# ECU.net
KiCad netlist of a schematic drawn in EAGLE
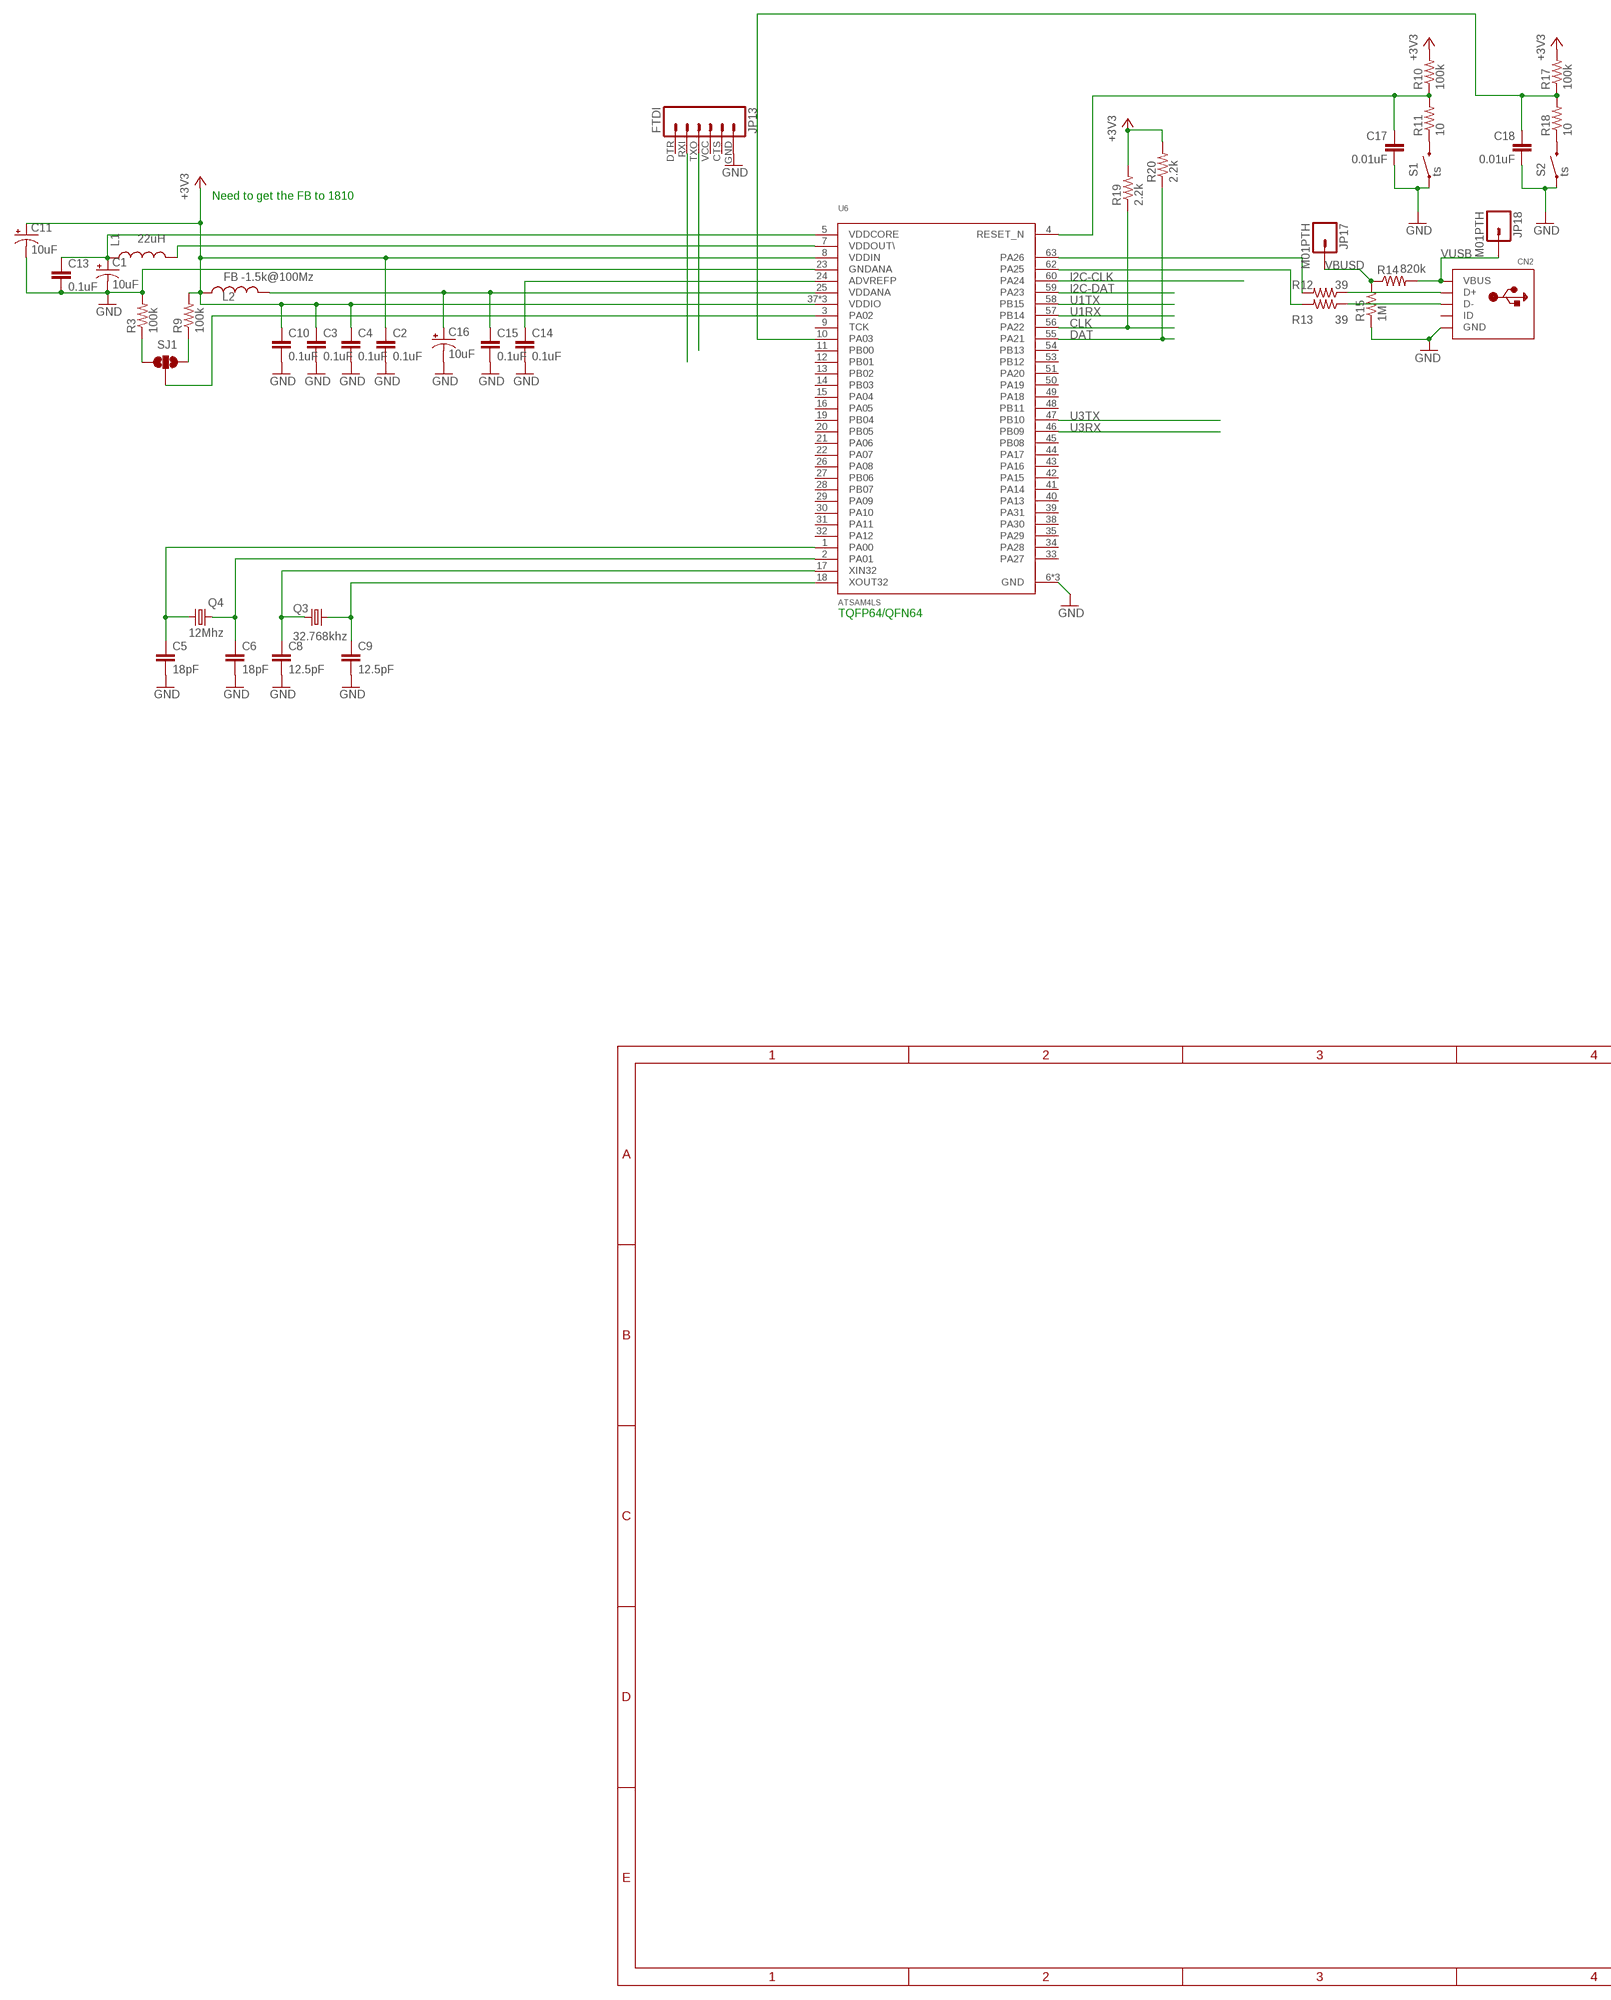
[diagram p0: schematic, sheet 1, part 1 of 2]
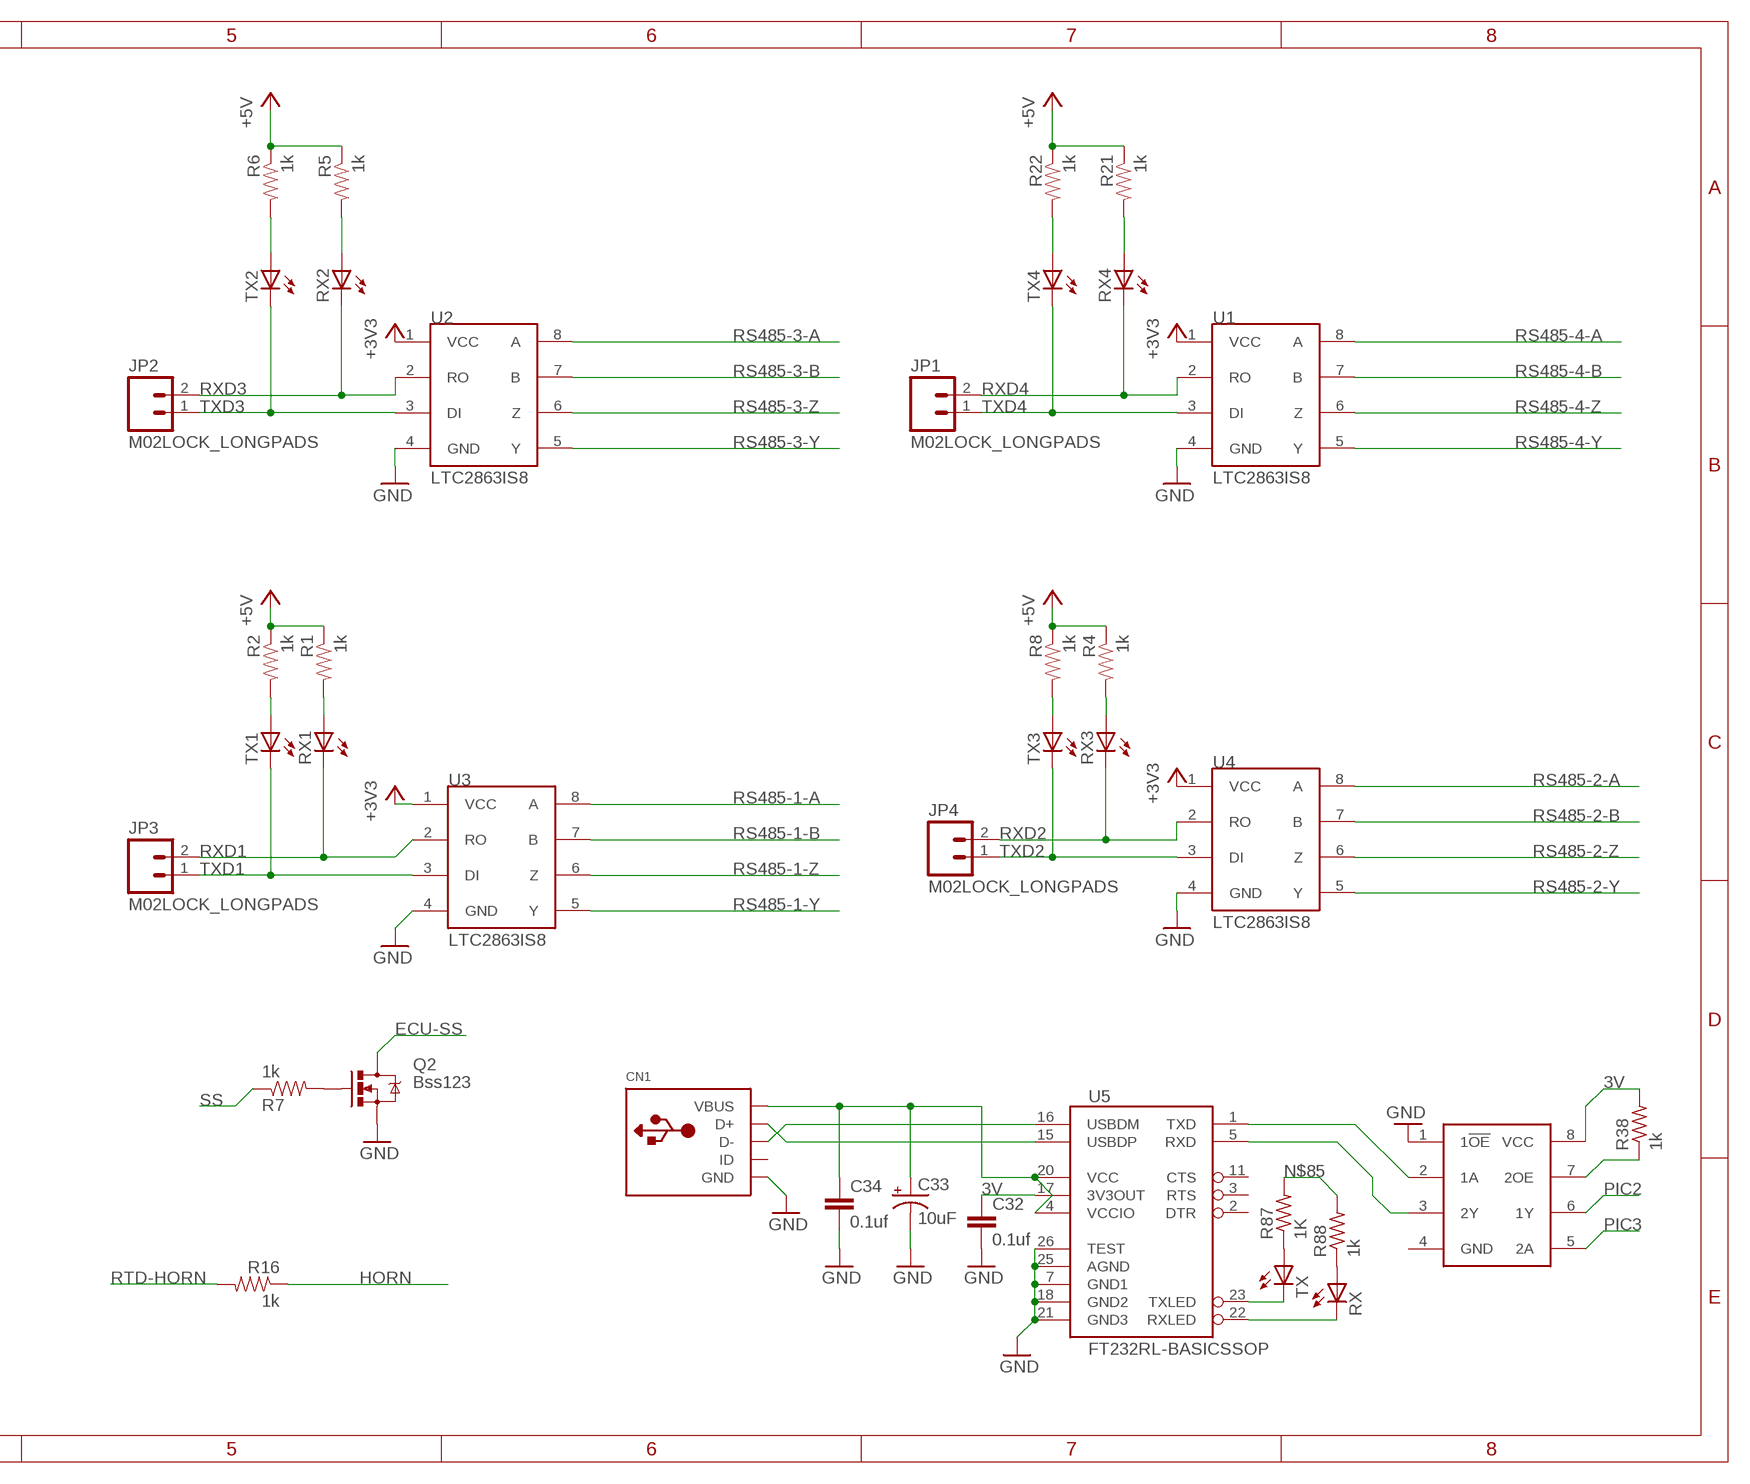
[diagram p1: schematic, sheet 1, part 2 of 2]
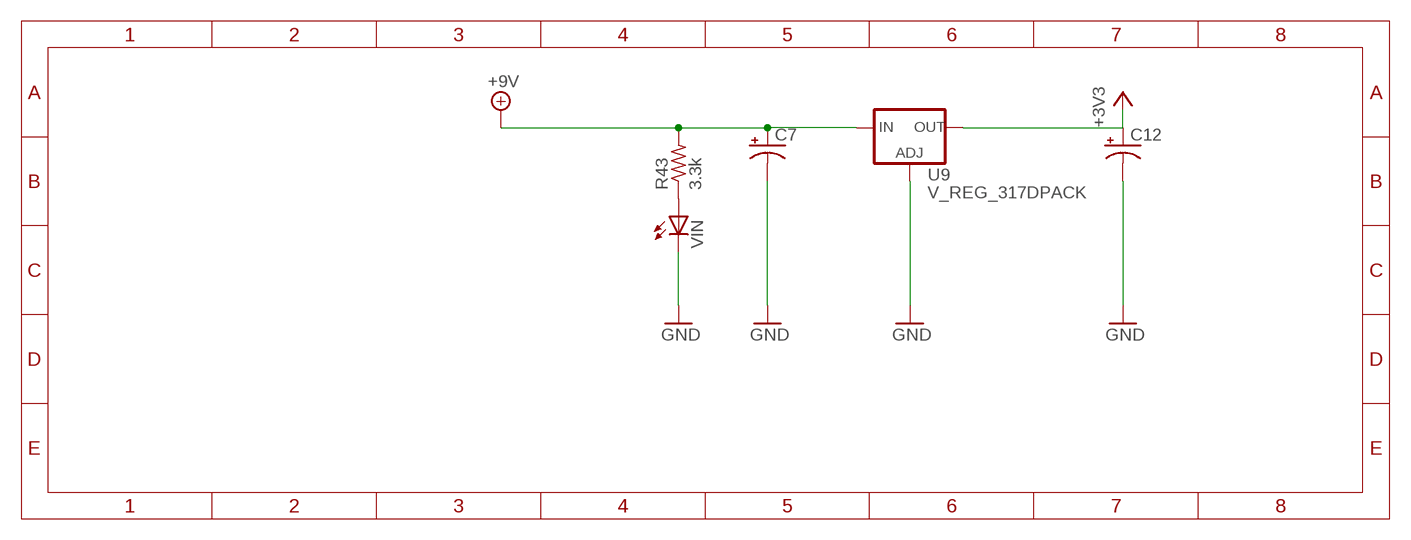
[diagram p2: schematic, sheet 2]
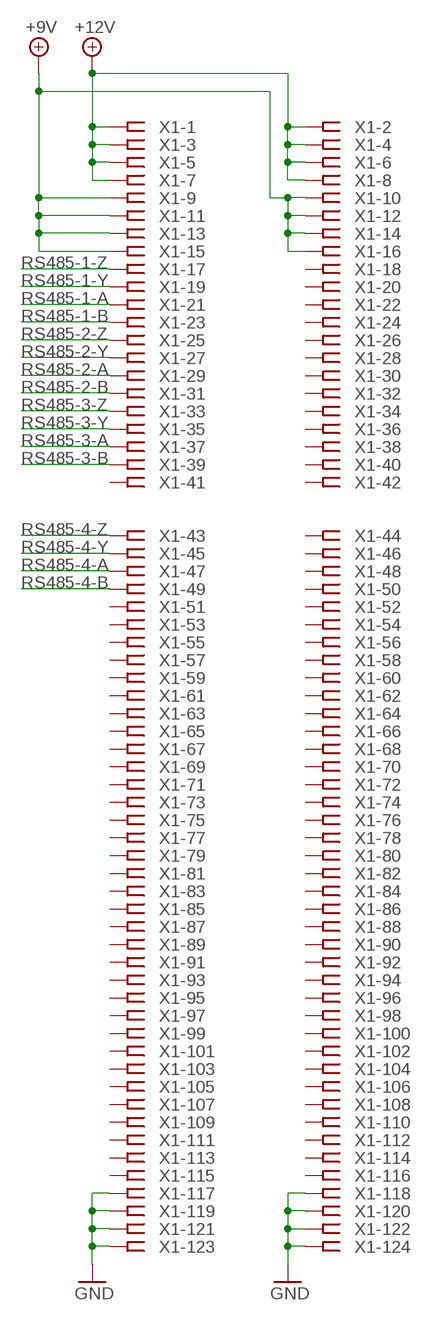
[diagram p3: schematic, sheet 3]

(export (version "E")
  (design (tool "Eeschema 10.0.6"))
  (components
    (comp (ref "X1")
      (value "AGP-3X3")
      (footprint "eagle-import:AGP-3X3")
      (libsource (lib "eagle-import") (part "AGP-3X3"))
    )
    (comp (ref "C7")
      (value "CAP_POL7343")
      (footprint "eagle-import:EIA7343")
      (libsource (lib "eagle-import") (part "SparkFun-Capacitors_CAP_POL7343"))
    )
    (comp (ref "C12")
      (value "CAP_POL3528")
      (footprint "eagle-import:EIA3528")
      (libsource (lib "eagle-import") (part "SparkFun-Capacitors_CAP_POL3528"))
    )
    (comp (ref "R43")
      (value "3.3k")
      (footprint "eagle-import:R0805")
      (libsource (lib "eagle-import") (part "R-US_R0805"))
    )
    (comp (ref "U9")
      (value "V_REG_317DPACK")
      (footprint "eagle-import:V-REG_DPACK")
      (libsource (lib "eagle-import") (part "V_REG_317DPACK"))
    )
    (comp (ref "VIN")
      (value "LEDCHIP-LED0805")
      (footprint "eagle-import:CHIP-LED0805")
      (libsource (lib "eagle-import") (part "LEDCHIP-LED0805"))
    )
    (comp (ref "C1")
      (value "10uF")
      (footprint "eagle-import:EIA3216")
      (libsource (lib "eagle-import") (part "SparkFun-Passives_CAP_POL1206"))
    )
    (comp (ref "C2")
      (value "0.1uF")
      (footprint "eagle-import:0805")
      (libsource (lib "eagle-import") (part "SparkFun-Passives_CAP0805"))
    )
    (comp (ref "C3")
      (value "0.1uF")
      (footprint "eagle-import:0805")
      (libsource (lib "eagle-import") (part "SparkFun-Passives_CAP0805"))
    )
    (comp (ref "C4")
      (value "0.1uF")
      (footprint "eagle-import:0805")
      (libsource (lib "eagle-import") (part "SparkFun-Passives_CAP0805"))
    )
    (comp (ref "C5")
      (value "18pF")
      (footprint "eagle-import:0805")
      (libsource (lib "eagle-import") (part "SparkFun-Passives_CAP0805"))
    )
    (comp (ref "C6")
      (value "18pF")
      (footprint "eagle-import:0805")
      (libsource (lib "eagle-import") (part "SparkFun-Passives_CAP0805"))
    )
    (comp (ref "C8")
      (value "12.5pF")
      (footprint "eagle-import:0805")
      (libsource (lib "eagle-import") (part "SparkFun-Passives_CAP0805"))
    )
    (comp (ref "C9")
      (value "12.5pF")
      (footprint "eagle-import:0805")
      (libsource (lib "eagle-import") (part "SparkFun-Passives_CAP0805"))
    )
    (comp (ref "C10")
      (value "0.1uF")
      (footprint "eagle-import:0805")
      (libsource (lib "eagle-import") (part "SparkFun-Passives_CAP0805"))
    )
    (comp (ref "C11")
      (value "10uF")
      (footprint "eagle-import:EIA3216")
      (libsource (lib "eagle-import") (part "10UF-16V-10%(TANT)"))
    )
    (comp (ref "C13")
      (value "0.1uF")
      (footprint "eagle-import:0805")
      (libsource (lib "eagle-import") (part "SparkFun-Passives_CAP0805"))
    )
    (comp (ref "C14")
      (value "0.1uF")
      (footprint "eagle-import:0805")
      (libsource (lib "eagle-import") (part "SparkFun-Passives_CAP0805"))
    )
    (comp (ref "C15")
      (value "0.1uF")
      (footprint "eagle-import:0805")
      (libsource (lib "eagle-import") (part "SparkFun-Passives_CAP0805"))
    )
    (comp (ref "C16")
      (value "10uF")
      (footprint "eagle-import:EIA3216")
      (libsource (lib "eagle-import") (part "SparkFun-Passives_CAP_POL1206"))
    )
    (comp (ref "C17")
      (value "0.01uF")
      (footprint "eagle-import:0805")
      (libsource (lib "eagle-import") (part "SparkFun-Passives_CAP0805"))
    )
    (comp (ref "C18")
      (value "0.01uF")
      (footprint "eagle-import:0805")
      (libsource (lib "eagle-import") (part "SparkFun-Passives_CAP0805"))
    )
    (comp (ref "C32")
      (value "0.1uf")
      (footprint "eagle-import:0805")
      (libsource (lib "eagle-import") (part "CAP0805"))
    )
    (comp (ref "C33")
      (value "10uF")
      (footprint "eagle-import:EIA3216")
      (libsource (lib "eagle-import") (part "CAP_POL1206"))
    )
    (comp (ref "C34")
      (value "0.1uf")
      (footprint "eagle-import:0805")
      (libsource (lib "eagle-import") (part "CAP0805"))
    )
    (comp (ref "CN1")
      (value "USBMOLEX")
      (footprint "eagle-import:USB-MINIB-THM-MOLEX")
      (libsource (lib "eagle-import") (part "USBMOLEX"))
    )
    (comp (ref "CN2")
      (value "USBMOLEX")
      (footprint "eagle-import:USB-MINIB-THM-MOLEX")
      (libsource (lib "eagle-import") (part "USBMOLEX"))
    )
    (comp (ref "JP1")
      (value "M02LOCK_LONGPADS")
      (footprint "eagle-import:1X02_LOCK_LONGPADS")
      (libsource (lib "eagle-import") (part "M02LOCK_LONGPADS"))
    )
    (comp (ref "JP2")
      (value "M02LOCK_LONGPADS")
      (footprint "eagle-import:1X02_LOCK_LONGPADS")
      (libsource (lib "eagle-import") (part "M02LOCK_LONGPADS"))
    )
    (comp (ref "JP3")
      (value "M02LOCK_LONGPADS")
      (footprint "eagle-import:1X02_LOCK_LONGPADS")
      (libsource (lib "eagle-import") (part "M02LOCK_LONGPADS"))
    )
    (comp (ref "JP4")
      (value "M02LOCK_LONGPADS")
      (footprint "eagle-import:1X02_LOCK_LONGPADS")
      (libsource (lib "eagle-import") (part "M02LOCK_LONGPADS"))
    )
    (comp (ref "JP13")
      (value "FTDI")
      (footprint "eagle-import:FTDI_BASIC")
      (libsource (lib "eagle-import") (part "FTDI_BASICPTH"))
    )
    (comp (ref "JP17")
      (value "M01PTH")
      (footprint "eagle-import:1X01")
      (libsource (lib "eagle-import") (part "M01PTH"))
    )
    (comp (ref "JP18")
      (value "M01PTH")
      (footprint "eagle-import:1X01")
      (libsource (lib "eagle-import") (part "M01PTH"))
    )
    (comp (ref "L1")
      (value "22uH")
      (footprint "eagle-import:0805")
      (libsource (lib "eagle-import") (part "INDUCTOR0805"))
    )
    (comp (ref "L2")
      (value "FB -1.5k@100Mz")
      (footprint "eagle-import:0805")
      (libsource (lib "eagle-import") (part "INDUCTOR0805"))
    )
    (comp (ref "Q2")
      (value "Bss123")
      (footprint "eagle-import:SOT23")
      (libsource (lib "eagle-import") (part "MOSFET-NCHANNELBSS123LT1G"))
    )
    (comp (ref "Q3")
      (value "32.768khz")
      (footprint "eagle-import:MM20SS")
      (libsource (lib "eagle-import") (part "CRYSTALMM20SS"))
    )
    (comp (ref "Q4")
      (value "12Mhz")
      (footprint "eagle-import:CTS406")
      (libsource (lib "eagle-import") (part "CRYSTALCTS406"))
    )
    (comp (ref "R1")
      (value "1k")
      (footprint "eagle-import:0805")
      (libsource (lib "eagle-import") (part "RESISTOR0805-RES"))
    )
    (comp (ref "R2")
      (value "1k")
      (footprint "eagle-import:0805")
      (libsource (lib "eagle-import") (part "RESISTOR0805-RES"))
    )
    (comp (ref "R3")
      (value "100k")
      (footprint "eagle-import:0805")
      (libsource (lib "eagle-import") (part "RESISTOR0805-RES"))
    )
    (comp (ref "R4")
      (value "1k")
      (footprint "eagle-import:0805")
      (libsource (lib "eagle-import") (part "RESISTOR0805-RES"))
    )
    (comp (ref "R5")
      (value "1k")
      (footprint "eagle-import:0805")
      (libsource (lib "eagle-import") (part "RESISTOR0805-RES"))
    )
    (comp (ref "R6")
      (value "1k")
      (footprint "eagle-import:0805")
      (libsource (lib "eagle-import") (part "RESISTOR0805-RES"))
    )
    (comp (ref "R7")
      (value "1k")
      (footprint "eagle-import:0805")
      (libsource (lib "eagle-import") (part "RESISTOR0805-RES"))
    )
    (comp (ref "R8")
      (value "1k")
      (footprint "eagle-import:0805")
      (libsource (lib "eagle-import") (part "RESISTOR0805-RES"))
    )
    (comp (ref "R9")
      (value "100k")
      (footprint "eagle-import:0805")
      (libsource (lib "eagle-import") (part "RESISTOR0805-RES"))
    )
    (comp (ref "R10")
      (value "100k")
      (footprint "eagle-import:0805")
      (libsource (lib "eagle-import") (part "RESISTOR0805-RES"))
    )
    (comp (ref "R11")
      (value "10")
      (footprint "eagle-import:0805")
      (libsource (lib "eagle-import") (part "RESISTOR0805-RES"))
    )
    (comp (ref "R12")
      (value "39")
      (footprint "eagle-import:0805")
      (libsource (lib "eagle-import") (part "RESISTOR0805-RES"))
    )
    (comp (ref "R13")
      (value "39")
      (footprint "eagle-import:0805")
      (libsource (lib "eagle-import") (part "RESISTOR0805-RES"))
    )
    (comp (ref "R14")
      (value "820k")
      (footprint "eagle-import:0805")
      (libsource (lib "eagle-import") (part "RESISTOR0805-RES"))
    )
    (comp (ref "R15")
      (value "1M")
      (footprint "eagle-import:0805")
      (libsource (lib "eagle-import") (part "RESISTOR0805-RES"))
    )
    (comp (ref "R16")
      (value "1k")
      (footprint "eagle-import:0805")
      (libsource (lib "eagle-import") (part "RESISTOR0805-RES"))
    )
    (comp (ref "R17")
      (value "100k")
      (footprint "eagle-import:0805")
      (libsource (lib "eagle-import") (part "RESISTOR0805-RES"))
    )
    (comp (ref "R18")
      (value "10")
      (footprint "eagle-import:0805")
      (libsource (lib "eagle-import") (part "RESISTOR0805-RES"))
    )
    (comp (ref "R19")
      (value "2.2k")
      (footprint "eagle-import:0805")
      (libsource (lib "eagle-import") (part "RESISTOR0805-RES"))
    )
    (comp (ref "R20")
      (value "2.2k")
      (footprint "eagle-import:0805")
      (libsource (lib "eagle-import") (part "RESISTOR0805-RES"))
    )
    (comp (ref "R21")
      (value "1k")
      (footprint "eagle-import:0805")
      (libsource (lib "eagle-import") (part "RESISTOR0805-RES"))
    )
    (comp (ref "R22")
      (value "1k")
      (footprint "eagle-import:0805")
      (libsource (lib "eagle-import") (part "RESISTOR0805-RES"))
    )
    (comp (ref "R38")
      (value "1k")
      (footprint "eagle-import:R0805")
      (libsource (lib "eagle-import") (part "R-US_R0805"))
    )
    (comp (ref "R87")
      (value "1K")
      (footprint "eagle-import:R0805")
      (libsource (lib "eagle-import") (part "R-US_R0805"))
    )
    (comp (ref "R88")
      (value "1k")
      (footprint "eagle-import:R0805")
      (libsource (lib "eagle-import") (part "R-US_R0805"))
    )
    (comp (ref "RX")
      (value "LEDCHIPLED_0805")
      (footprint "eagle-import:CHIPLED_0805")
      (libsource (lib "eagle-import") (part "LEDCHIPLED_0805"))
    )
    (comp (ref "RX1")
      (value "LEDCHIP-LED0805")
      (footprint "eagle-import:CHIP-LED0805")
      (libsource (lib "eagle-import") (part "LEDCHIP-LED0805"))
    )
    (comp (ref "RX2")
      (value "LEDCHIP-LED0805")
      (footprint "eagle-import:CHIP-LED0805")
      (libsource (lib "eagle-import") (part "LEDCHIP-LED0805"))
    )
    (comp (ref "RX3")
      (value "LEDCHIP-LED0805")
      (footprint "eagle-import:CHIP-LED0805")
      (libsource (lib "eagle-import") (part "LEDCHIP-LED0805"))
    )
    (comp (ref "RX4")
      (value "LEDCHIP-LED0805")
      (footprint "eagle-import:CHIP-LED0805")
      (libsource (lib "eagle-import") (part "LEDCHIP-LED0805"))
    )
    (comp (ref "S1")
      (value "ts")
      (footprint "eagle-import:TACTILE-PTH-SIDEEZ")
      (libsource (lib "eagle-import") (part "SWITCH-MOMENTARY-2SIDE_EZ"))
    )
    (comp (ref "S2")
      (value "ts")
      (footprint "eagle-import:TACTILE-PTH-SIDEEZ")
      (libsource (lib "eagle-import") (part "SWITCH-MOMENTARY-2SIDE_EZ"))
    )
    (comp (ref "SJ1")
      (value "SOLDERJUMPER_2WAYS")
      (footprint "eagle-import:SJ_3")
      (libsource (lib "eagle-import") (part "SOLDERJUMPER_2WAYS"))
    )
    (comp (ref "TX")
      (value "LEDCHIPLED_0805")
      (footprint "eagle-import:CHIPLED_0805")
      (libsource (lib "eagle-import") (part "LEDCHIPLED_0805"))
    )
    (comp (ref "TX1")
      (value "LEDCHIP-LED0805")
      (footprint "eagle-import:CHIP-LED0805")
      (libsource (lib "eagle-import") (part "LEDCHIP-LED0805"))
    )
    (comp (ref "TX2")
      (value "LEDCHIP-LED0805")
      (footprint "eagle-import:CHIP-LED0805")
      (libsource (lib "eagle-import") (part "LEDCHIP-LED0805"))
    )
    (comp (ref "TX3")
      (value "LEDCHIP-LED0805")
      (footprint "eagle-import:CHIP-LED0805")
      (libsource (lib "eagle-import") (part "LEDCHIP-LED0805"))
    )
    (comp (ref "TX4")
      (value "LEDCHIP-LED0805")
      (footprint "eagle-import:CHIP-LED0805")
      (libsource (lib "eagle-import") (part "LEDCHIP-LED0805"))
    )
    (comp (ref "U1")
      (value "LTC2863IS8")
      (footprint "eagle-import:SO08")
      (libsource (lib "eagle-import") (part "ISL83077"))
    )
    (comp (ref "U2")
      (value "LTC2863IS8")
      (footprint "eagle-import:SO08")
      (libsource (lib "eagle-import") (part "ISL83077"))
    )
    (comp (ref "U3")
      (value "LTC2863IS8")
      (footprint "eagle-import:SO08")
      (libsource (lib "eagle-import") (part "ISL83077"))
    )
    (comp (ref "U4")
      (value "LTC2863IS8")
      (footprint "eagle-import:SO08")
      (libsource (lib "eagle-import") (part "ISL83077"))
    )
    (comp (ref "U5")
      (value "FT232RL-BASICSSOP")
      (footprint "eagle-import:SSOP28DB")
      (libsource (lib "eagle-import") (part "FT232RL-BASICSSOP"))
    )
    (comp (ref "U6")
      (value "ATSAM4LS")
      (footprint "eagle-import:TQFP-64")
      (libsource (lib "eagle-import") (part "SAM4L"))
    )
    (comp (ref "U14")
      (value "SN74LVC2G241DCTR")
      (footprint "eagle-import:VFSOP-8")
      (libsource (lib "eagle-import") (part "SN74LVC2G241DCTR"))
    )
  )
  (nets
    (net (code "1") (name "+3V3") (class "Default")
      (node (ref "C10") (pin "1") (pinfunction "1_1") (pintype "passive"))
      (node (ref "C11") (pin "A") (pinfunction "+_A") (pintype "passive"))
      (node (ref "C12") (pin "A") (pinfunction "+_A") (pintype "passive"))
      (node (ref "C2") (pin "1") (pinfunction "1_1") (pintype "passive"))
      (node (ref "C3") (pin "1") (pinfunction "1_1") (pintype "passive"))
      (node (ref "C4") (pin "1") (pinfunction "1_1") (pintype "passive"))
      (node (ref "L2") (pin "1") (pinfunction "1_1") (pintype "passive"))
      (node (ref "R10") (pin "2") (pinfunction "2_2") (pintype "passive"))
      (node (ref "R17") (pin "2") (pinfunction "2_2") (pintype "passive"))
      (node (ref "R19") (pin "2") (pinfunction "2_2") (pintype "passive"))
      (node (ref "R20") (pin "2") (pinfunction "2_2") (pintype "passive"))
      (node (ref "R9") (pin "2") (pinfunction "2_2") (pintype "passive"))
      (node (ref "U1") (pin "1") (pinfunction "VCC_1") (pintype "bidirectional"))
      (node (ref "U2") (pin "1") (pinfunction "VCC_1") (pintype "bidirectional"))
      (node (ref "U3") (pin "1") (pinfunction "VCC_1") (pintype "bidirectional"))
      (node (ref "U4") (pin "1") (pinfunction "VCC_1") (pintype "bidirectional"))
      (node (ref "U6") (pin "37") (pinfunction "VDDIO_37") (pintype "bidirectional"))
      (node (ref "U6") (pin "52") (pinfunction "VDDIO_52") (pintype "bidirectional"))
      (node (ref "U6") (pin "61") (pinfunction "VDDIO_61") (pintype "bidirectional"))
      (node (ref "U6") (pin "8") (pinfunction "VDDIN_8") (pintype "bidirectional"))
      (node (ref "U9") (pin "4") (pinfunction "OUT_4") (pintype "output"))
    )
    (net (code "2") (name "+5V") (class "Default")
      (node (ref "R1") (pin "1") (pinfunction "1_1") (pintype "passive"))
      (node (ref "R2") (pin "1") (pinfunction "1_1") (pintype "passive"))
      (node (ref "R21") (pin "1") (pinfunction "1_1") (pintype "passive"))
      (node (ref "R22") (pin "1") (pinfunction "1_1") (pintype "passive"))
      (node (ref "R4") (pin "1") (pinfunction "1_1") (pintype "passive"))
      (node (ref "R5") (pin "1") (pinfunction "1_1") (pintype "passive"))
      (node (ref "R6") (pin "1") (pinfunction "1_1") (pintype "passive"))
      (node (ref "R8") (pin "1") (pinfunction "1_1") (pintype "passive"))
    )
    (net (code "3") (name "+9V") (class "Default")
      (node (ref "C7") (pin "A") (pinfunction "+_A") (pintype "passive"))
      (node (ref "R43") (pin "2") (pinfunction "2_2") (pintype "passive"))
      (node (ref "U9") (pin "3") (pinfunction "IN_3") (pintype "input"))
      (node (ref "X1") (pin "10") (pinfunction "P_10") (pintype "passive"))
      (node (ref "X1") (pin "11") (pinfunction "P_11") (pintype "passive"))
      (node (ref "X1") (pin "12") (pinfunction "P_12") (pintype "passive"))
      (node (ref "X1") (pin "13") (pinfunction "P_13") (pintype "passive"))
      (node (ref "X1") (pin "14") (pinfunction "P_14") (pintype "passive"))
      (node (ref "X1") (pin "15") (pinfunction "P_15") (pintype "passive"))
      (node (ref "X1") (pin "16") (pinfunction "P_16") (pintype "passive"))
      (node (ref "X1") (pin "9") (pinfunction "P_9") (pintype "passive"))
    )
    (net (code "4") (name "+12V") (class "Default")
      (node (ref "X1") (pin "1") (pinfunction "P_1") (pintype "passive"))
      (node (ref "X1") (pin "2") (pinfunction "P_2") (pintype "passive"))
      (node (ref "X1") (pin "3") (pinfunction "P_3") (pintype "passive"))
      (node (ref "X1") (pin "4") (pinfunction "P_4") (pintype "passive"))
      (node (ref "X1") (pin "5") (pinfunction "P_5") (pintype "passive"))
      (node (ref "X1") (pin "6") (pinfunction "P_6") (pintype "passive"))
      (node (ref "X1") (pin "7") (pinfunction "P_7") (pintype "passive"))
      (node (ref "X1") (pin "8") (pinfunction "P_8") (pintype "passive"))
    )
    (net (code "5") (name "3V") (class "Default")
      (node (ref "C32") (pin "1") (pinfunction "1_1") (pintype "passive"))
      (node (ref "R38") (pin "2") (pinfunction "2_2") (pintype "passive"))
      (node (ref "U14") (pin "8") (pinfunction "VCC_8") (pintype "bidirectional"))
      (node (ref "U5") (pin "17") (pinfunction "3V3OUT_17") (pintype "output"))
    )
    (net (code "6") (name "CLK") (class "Default")
      (node (ref "R19") (pin "1") (pinfunction "1_1") (pintype "passive"))
      (node (ref "U6") (pin "56") (pinfunction "PA22_56") (pintype "bidirectional"))
    )
    (net (code "7") (name "DAT") (class "Default")
      (node (ref "R20") (pin "1") (pinfunction "1_1") (pintype "passive"))
      (node (ref "U6") (pin "55") (pinfunction "PA21_55") (pintype "bidirectional"))
    )
    (net (code "8") (name "ECU-SS") (class "Default")
      (node (ref "Q2") (pin "3") (pinfunction "D_3") (pintype "passive"))
    )
    (net (code "9") (name "GND") (class "Default")
      (node (ref "C1") (pin "C") (pinfunction "-_C") (pintype "passive"))
      (node (ref "C10") (pin "2") (pinfunction "2_2") (pintype "passive"))
      (node (ref "C11") (pin "C") (pinfunction "-_C") (pintype "passive"))
      (node (ref "C12") (pin "C") (pinfunction "-_C") (pintype "passive"))
      (node (ref "C13") (pin "2") (pinfunction "2_2") (pintype "passive"))
      (node (ref "C14") (pin "2") (pinfunction "2_2") (pintype "passive"))
      (node (ref "C15") (pin "2") (pinfunction "2_2") (pintype "passive"))
      (node (ref "C16") (pin "C") (pinfunction "-_C") (pintype "passive"))
      (node (ref "C17") (pin "2") (pinfunction "2_2") (pintype "passive"))
      (node (ref "C18") (pin "2") (pinfunction "2_2") (pintype "passive"))
      (node (ref "C2") (pin "2") (pinfunction "2_2") (pintype "passive"))
      (node (ref "C3") (pin "2") (pinfunction "2_2") (pintype "passive"))
      (node (ref "C32") (pin "2") (pinfunction "2_2") (pintype "passive"))
      (node (ref "C33") (pin "C") (pinfunction "-_C") (pintype "passive"))
      (node (ref "C34") (pin "2") (pinfunction "2_2") (pintype "passive"))
      (node (ref "C4") (pin "2") (pinfunction "2_2") (pintype "passive"))
      (node (ref "C5") (pin "2") (pinfunction "2_2") (pintype "passive"))
      (node (ref "C6") (pin "2") (pinfunction "2_2") (pintype "passive"))
      (node (ref "C7") (pin "C") (pinfunction "-_C") (pintype "passive"))
      (node (ref "C8") (pin "2") (pinfunction "2_2") (pintype "passive"))
      (node (ref "C9") (pin "2") (pinfunction "2_2") (pintype "passive"))
      (node (ref "CN1") (pin "GND") (pinfunction "GND_GND") (pintype "power_in"))
      (node (ref "CN2") (pin "GND") (pinfunction "GND_GND") (pintype "power_in"))
      (node (ref "JP13") (pin "GND") (pinfunction "6_GND") (pintype "passive"))
      (node (ref "Q2") (pin "2") (pinfunction "S_2") (pintype "passive"))
      (node (ref "R15") (pin "1") (pinfunction "1_1") (pintype "passive"))
      (node (ref "R3") (pin "2") (pinfunction "2_2") (pintype "passive"))
      (node (ref "S1") (pin "1") (pinfunction "1_1") (pintype "passive"))
      (node (ref "S2") (pin "1") (pinfunction "1_1") (pintype "passive"))
      (node (ref "U1") (pin "4") (pinfunction "GND_4") (pintype "bidirectional"))
      (node (ref "U14") (pin "1") (pinfunction "1~{OE}_1") (pintype "bidirectional"))
      (node (ref "U2") (pin "4") (pinfunction "GND_4") (pintype "bidirectional"))
      (node (ref "U3") (pin "4") (pinfunction "GND_4") (pintype "bidirectional"))
      (node (ref "U4") (pin "4") (pinfunction "GND_4") (pintype "bidirectional"))
      (node (ref "U5") (pin "18") (pinfunction "GND2_18") (pintype "power_in"))
      (node (ref "U5") (pin "21") (pinfunction "GND3_21") (pintype "power_in"))
      (node (ref "U5") (pin "25") (pinfunction "AGND_25") (pintype "power_in"))
      (node (ref "U5") (pin "26") (pinfunction "TEST_26") (pintype "input"))
      (node (ref "U5") (pin "7") (pinfunction "GND1_7") (pintype "power_in"))
      (node (ref "U6") (pin "23") (pinfunction "GNDANA_23") (pintype "bidirectional"))
      (node (ref "U6") (pin "36") (pinfunction "GND_36") (pintype "bidirectional"))
      (node (ref "U6") (pin "6") (pinfunction "GND_6") (pintype "bidirectional"))
      (node (ref "U6") (pin "64") (pinfunction "GND_64") (pintype "bidirectional"))
      (node (ref "U9") (pin "1") (pinfunction "ADJ_1") (pintype "input"))
      (node (ref "VIN") (pin "C") (pinfunction "C_C") (pintype "passive"))
      (node (ref "X1") (pin "117") (pinfunction "P_117") (pintype "passive"))
      (node (ref "X1") (pin "118") (pinfunction "P_118") (pintype "passive"))
      (node (ref "X1") (pin "119") (pinfunction "P_119") (pintype "passive"))
      (node (ref "X1") (pin "120") (pinfunction "P_120") (pintype "passive"))
      (node (ref "X1") (pin "121") (pinfunction "P_121") (pintype "passive"))
      (node (ref "X1") (pin "122") (pinfunction "P_122") (pintype "passive"))
      (node (ref "X1") (pin "123") (pinfunction "P_123") (pintype "passive"))
      (node (ref "X1") (pin "124") (pinfunction "P_124") (pintype "passive"))
    )
    (net (code "10") (name "HORN") (class "Default")
      (node (ref "R16") (pin "1") (pinfunction "1_1") (pintype "passive"))
    )
    (net (code "11") (name "I2C-CLK") (class "Default")
      (node (ref "U6") (pin "60") (pinfunction "PA24_60") (pintype "bidirectional"))
    )
    (net (code "12") (name "I2C-DAT") (class "Default")
      (node (ref "U6") (pin "59") (pinfunction "PA23_59") (pintype "bidirectional"))
    )
    (net (code "13") (name "N$85") (class "Default")
      (node (ref "C33") (pin "A") (pinfunction "+_A") (pintype "passive"))
      (node (ref "C34") (pin "1") (pinfunction "1_1") (pintype "passive"))
      (node (ref "CN1") (pin "VBUS") (pinfunction "VBUS_VBUS") (pintype "power_in"))
      (node (ref "R87") (pin "2") (pinfunction "2_2") (pintype "passive"))
      (node (ref "R88") (pin "2") (pinfunction "2_2") (pintype "passive"))
      (node (ref "U5") (pin "20") (pinfunction "VCC_20") (pintype "power_in"))
      (node (ref "U5") (pin "4") (pinfunction "VCCIO_4") (pintype "power_in"))
    )
    (net (code "14") (name "Net-(C1-+)") (class "Default")
      (node (ref "C1") (pin "A") (pinfunction "+_A") (pintype "passive"))
      (node (ref "C13") (pin "1") (pinfunction "1_1") (pintype "passive"))
      (node (ref "L1") (pin "1") (pinfunction "1_1") (pintype "passive"))
      (node (ref "U6") (pin "5") (pinfunction "VDDCORE_5") (pintype "bidirectional"))
    )
    (net (code "15") (name "Net-(C16-+)") (class "Default")
      (node (ref "C15") (pin "1") (pinfunction "1_1") (pintype "passive"))
      (node (ref "C16") (pin "A") (pinfunction "+_A") (pintype "passive"))
      (node (ref "L2") (pin "2") (pinfunction "2_2") (pintype "passive"))
      (node (ref "U6") (pin "25") (pinfunction "VDDANA_25") (pintype "bidirectional"))
    )
    (net (code "16") (name "Net-(CN2-PadD+)") (class "Default")
      (node (ref "CN2") (pin "D+") (pinfunction "D+_D+") (pintype "bidirectional"))
      (node (ref "R12") (pin "1") (pinfunction "1_1") (pintype "passive"))
    )
    (net (code "17") (name "Net-(CN2-PadD-)") (class "Default")
      (node (ref "CN2") (pin "D-") (pinfunction "D-_D-") (pintype "bidirectional"))
      (node (ref "R13") (pin "1") (pinfunction "1_1") (pintype "passive"))
    )
    (net (code "18") (name "Net-(Q2-G)") (class "Default")
      (node (ref "Q2") (pin "1") (pinfunction "G_1") (pintype "passive"))
      (node (ref "R7") (pin "2") (pinfunction "2_2") (pintype "passive"))
    )
    (net (code "19") (name "Net-(Q3-2)") (class "Default")
      (node (ref "C9") (pin "1") (pinfunction "1_1") (pintype "passive"))
      (node (ref "Q3") (pin "4") (pinfunction "2_4") (pintype "passive"))
      (node (ref "U6") (pin "18") (pinfunction "XOUT32_18") (pintype "bidirectional"))
    )
    (net (code "20") (name "Net-(Q4-2)") (class "Default")
      (node (ref "C5") (pin "1") (pinfunction "1_1") (pintype "passive"))
      (node (ref "Q4") (pin "3") (pinfunction "2_3") (pintype "passive"))
      (node (ref "U6") (pin "1") (pinfunction "PA00_1") (pintype "bidirectional"))
    )
    (net (code "21") (name "Net-(R1-Pad2)") (class "Default")
      (node (ref "R1") (pin "2") (pinfunction "2_2") (pintype "passive"))
      (node (ref "RX1") (pin "A") (pinfunction "A_A") (pintype "passive"))
    )
    (net (code "22") (name "Net-(R2-Pad2)") (class "Default")
      (node (ref "R2") (pin "2") (pinfunction "2_2") (pintype "passive"))
      (node (ref "TX1") (pin "A") (pinfunction "A_A") (pintype "passive"))
    )
    (net (code "23") (name "Net-(R3-Pad1)") (class "Default")
      (node (ref "R3") (pin "1") (pinfunction "1_1") (pintype "passive"))
      (node (ref "SJ1") (pin "3") (pinfunction "3_3") (pintype "passive"))
    )
    (net (code "24") (name "Net-(R4-Pad2)") (class "Default")
      (node (ref "R4") (pin "2") (pinfunction "2_2") (pintype "passive"))
      (node (ref "RX3") (pin "A") (pinfunction "A_A") (pintype "passive"))
    )
    (net (code "25") (name "Net-(R5-Pad2)") (class "Default")
      (node (ref "R5") (pin "2") (pinfunction "2_2") (pintype "passive"))
      (node (ref "RX2") (pin "A") (pinfunction "A_A") (pintype "passive"))
    )
    (net (code "26") (name "Net-(R6-Pad2)") (class "Default")
      (node (ref "R6") (pin "2") (pinfunction "2_2") (pintype "passive"))
      (node (ref "TX2") (pin "A") (pinfunction "A_A") (pintype "passive"))
    )
    (net (code "27") (name "Net-(R8-Pad2)") (class "Default")
      (node (ref "R8") (pin "2") (pinfunction "2_2") (pintype "passive"))
      (node (ref "TX3") (pin "A") (pinfunction "A_A") (pintype "passive"))
    )
    (net (code "28") (name "Net-(R9-Pad1)") (class "Default")
      (node (ref "R9") (pin "1") (pinfunction "1_1") (pintype "passive"))
      (node (ref "SJ1") (pin "1") (pinfunction "1_1") (pintype "passive"))
    )
    (net (code "29") (name "Net-(R11-Pad1)") (class "Default")
      (node (ref "R11") (pin "1") (pinfunction "1_1") (pintype "passive"))
      (node (ref "S1") (pin "2") (pinfunction "2_2") (pintype "passive"))
    )
    (net (code "30") (name "Net-(R18-Pad1)") (class "Default")
      (node (ref "R18") (pin "1") (pinfunction "1_1") (pintype "passive"))
      (node (ref "S2") (pin "2") (pinfunction "2_2") (pintype "passive"))
    )
    (net (code "31") (name "Net-(R21-Pad2)") (class "Default")
      (node (ref "R21") (pin "2") (pinfunction "2_2") (pintype "passive"))
      (node (ref "RX4") (pin "A") (pinfunction "A_A") (pintype "passive"))
    )
    (net (code "32") (name "Net-(R22-Pad2)") (class "Default")
      (node (ref "R22") (pin "2") (pinfunction "2_2") (pintype "passive"))
      (node (ref "TX4") (pin "A") (pinfunction "A_A") (pintype "passive"))
    )
    (net (code "33") (name "Net-(R43-Pad1)") (class "Default")
      (node (ref "R43") (pin "1") (pinfunction "1_1") (pintype "passive"))
      (node (ref "VIN") (pin "A") (pinfunction "A_A") (pintype "passive"))
    )
    (net (code "34") (name "Net-(R87-Pad1)") (class "Default")
      (node (ref "R87") (pin "1") (pinfunction "1_1") (pintype "passive"))
      (node (ref "TX") (pin "A") (pinfunction "A_A") (pintype "passive"))
    )
    (net (code "35") (name "Net-(R88-Pad1)") (class "Default")
      (node (ref "R88") (pin "1") (pinfunction "1_1") (pintype "passive"))
      (node (ref "RX") (pin "A") (pinfunction "A_A") (pintype "passive"))
    )
    (net (code "36") (name "Net-(U5-RXLED)") (class "Default")
      (node (ref "RX") (pin "C") (pinfunction "C_C") (pintype "passive"))
      (node (ref "U5") (pin "22") (pinfunction "RXLED_22") (pintype "bidirectional"))
    )
    (net (code "37") (name "Net-(U5-TXLED)") (class "Default")
      (node (ref "TX") (pin "C") (pinfunction "C_C") (pintype "passive"))
      (node (ref "U5") (pin "23") (pinfunction "TXLED_23") (pintype "bidirectional"))
    )
    (net (code "38") (name "Net-(U5-USBDM)") (class "Default")
      (node (ref "CN1") (pin "D-") (pinfunction "D-_D-") (pintype "bidirectional"))
      (node (ref "U5") (pin "16") (pinfunction "USBDM_16") (pintype "bidirectional"))
    )
    (net (code "39") (name "Net-(U5-USBDP)") (class "Default")
      (node (ref "CN1") (pin "D+") (pinfunction "D+_D+") (pintype "bidirectional"))
      (node (ref "U5") (pin "15") (pinfunction "USBDP_15") (pintype "bidirectional"))
    )
    (net (code "40") (name "Net-(U6-ADVREFP)") (class "Default")
      (node (ref "C14") (pin "1") (pinfunction "1_1") (pintype "passive"))
      (node (ref "U6") (pin "24") (pinfunction "ADVREFP_24") (pintype "bidirectional"))
    )
    (net (code "41") (name "Net-(U6-PA01)") (class "Default")
      (node (ref "C6") (pin "1") (pinfunction "1_1") (pintype "passive"))
      (node (ref "Q4") (pin "1") (pinfunction "1_1") (pintype "passive"))
      (node (ref "U6") (pin "2") (pinfunction "PA01_2") (pintype "bidirectional"))
    )
    (net (code "42") (name "Net-(U6-PA02)") (class "Default")
      (node (ref "SJ1") (pin "2") (pinfunction "2_2") (pintype "passive"))
      (node (ref "U6") (pin "3") (pinfunction "PA02_3") (pintype "bidirectional"))
    )
    (net (code "43") (name "Net-(U6-PA03)") (class "Default")
      (node (ref "C18") (pin "1") (pinfunction "1_1") (pintype "passive"))
      (node (ref "R17") (pin "1") (pinfunction "1_1") (pintype "passive"))
      (node (ref "R18") (pin "2") (pinfunction "2_2") (pintype "passive"))
      (node (ref "U6") (pin "10") (pinfunction "PA03_10") (pintype "bidirectional"))
    )
    (net (code "44") (name "Net-(U6-PA25)") (class "Default")
      (node (ref "R13") (pin "2") (pinfunction "2_2") (pintype "passive"))
      (node (ref "U6") (pin "62") (pinfunction "PA25_62") (pintype "bidirectional"))
    )
    (net (code "45") (name "Net-(U6-PA26)") (class "Default")
      (node (ref "R12") (pin "2") (pinfunction "2_2") (pintype "passive"))
      (node (ref "U6") (pin "63") (pinfunction "PA26_63") (pintype "bidirectional"))
    )
    (net (code "46") (name "Net-(U6-RESET_N)") (class "Default")
      (node (ref "C17") (pin "1") (pinfunction "1_1") (pintype "passive"))
      (node (ref "R10") (pin "1") (pinfunction "1_1") (pintype "passive"))
      (node (ref "R11") (pin "2") (pinfunction "2_2") (pintype "passive"))
      (node (ref "U6") (pin "4") (pinfunction "RESET_N_4") (pintype "bidirectional"))
    )
    (net (code "47") (name "Net-(U6-VDDOUT\\)") (class "Default")
      (node (ref "L1") (pin "2") (pinfunction "2_2") (pintype "passive"))
      (node (ref "U6") (pin "7") (pinfunction "VDDOUT\\_7") (pintype "bidirectional"))
    )
    (net (code "48") (name "Net-(U6-XIN32)") (class "Default")
      (node (ref "C8") (pin "1") (pinfunction "1_1") (pintype "passive"))
      (node (ref "Q3") (pin "1") (pinfunction "1_1") (pintype "passive"))
      (node (ref "U6") (pin "17") (pinfunction "XIN32_17") (pintype "bidirectional"))
    )
    (net (code "49") (name "Net-(U14-1A)") (class "Default")
      (node (ref "U14") (pin "2") (pinfunction "1A_2") (pintype "bidirectional"))
      (node (ref "U5") (pin "1") (pinfunction "TXD_1") (pintype "output"))
    )
    (net (code "50") (name "Net-(U14-2OE)") (class "Default")
      (node (ref "R38") (pin "1") (pinfunction "1_1") (pintype "passive"))
      (node (ref "U14") (pin "7") (pinfunction "2OE_7") (pintype "bidirectional"))
    )
    (net (code "51") (name "Net-(U14-2Y)") (class "Default")
      (node (ref "U14") (pin "3") (pinfunction "2Y_3") (pintype "bidirectional"))
      (node (ref "U5") (pin "5") (pinfunction "RXD_5") (pintype "input"))
    )
    (net (code "52") (name "PIC2") (class "Default")
      (node (ref "U14") (pin "6") (pinfunction "1Y_6") (pintype "bidirectional"))
    )
    (net (code "53") (name "PIC3") (class "Default")
      (node (ref "U14") (pin "5") (pinfunction "2A_5") (pintype "bidirectional"))
    )
    (net (code "54") (name "RS485-1-A") (class "Default")
      (node (ref "U3") (pin "8") (pinfunction "A_8") (pintype "bidirectional"))
      (node (ref "X1") (pin "21") (pinfunction "P_21") (pintype "passive"))
    )
    (net (code "55") (name "RS485-1-B") (class "Default")
      (node (ref "U3") (pin "7") (pinfunction "B_7") (pintype "bidirectional"))
      (node (ref "X1") (pin "23") (pinfunction "P_23") (pintype "passive"))
    )
    (net (code "56") (name "RS485-1-Y") (class "Default")
      (node (ref "U3") (pin "5") (pinfunction "Y_5") (pintype "bidirectional"))
      (node (ref "X1") (pin "19") (pinfunction "P_19") (pintype "passive"))
    )
    (net (code "57") (name "RS485-1-Z") (class "Default")
      (node (ref "U3") (pin "6") (pinfunction "Z_6") (pintype "bidirectional"))
      (node (ref "X1") (pin "17") (pinfunction "P_17") (pintype "passive"))
    )
    (net (code "58") (name "RS485-2-A") (class "Default")
      (node (ref "U4") (pin "8") (pinfunction "A_8") (pintype "bidirectional"))
      (node (ref "X1") (pin "29") (pinfunction "P_29") (pintype "passive"))
    )
    (net (code "59") (name "RS485-2-B") (class "Default")
      (node (ref "U4") (pin "7") (pinfunction "B_7") (pintype "bidirectional"))
      (node (ref "X1") (pin "31") (pinfunction "P_31") (pintype "passive"))
    )
    (net (code "60") (name "RS485-2-Y") (class "Default")
      (node (ref "U4") (pin "5") (pinfunction "Y_5") (pintype "bidirectional"))
      (node (ref "X1") (pin "27") (pinfunction "P_27") (pintype "passive"))
    )
    (net (code "61") (name "RS485-2-Z") (class "Default")
      (node (ref "U4") (pin "6") (pinfunction "Z_6") (pintype "bidirectional"))
      (node (ref "X1") (pin "25") (pinfunction "P_25") (pintype "passive"))
    )
    (net (code "62") (name "RS485-3-A") (class "Default")
      (node (ref "U2") (pin "8") (pinfunction "A_8") (pintype "bidirectional"))
      (node (ref "X1") (pin "37") (pinfunction "P_37") (pintype "passive"))
    )
    (net (code "63") (name "RS485-3-B") (class "Default")
      (node (ref "U2") (pin "7") (pinfunction "B_7") (pintype "bidirectional"))
      (node (ref "X1") (pin "39") (pinfunction "P_39") (pintype "passive"))
    )
    (net (code "64") (name "RS485-3-Y") (class "Default")
      (node (ref "U2") (pin "5") (pinfunction "Y_5") (pintype "bidirectional"))
      (node (ref "X1") (pin "35") (pinfunction "P_35") (pintype "passive"))
    )
    (net (code "65") (name "RS485-3-Z") (class "Default")
      (node (ref "U2") (pin "6") (pinfunction "Z_6") (pintype "bidirectional"))
      (node (ref "X1") (pin "33") (pinfunction "P_33") (pintype "passive"))
    )
    (net (code "66") (name "RS485-4-A") (class "Default")
      (node (ref "U1") (pin "8") (pinfunction "A_8") (pintype "bidirectional"))
      (node (ref "X1") (pin "47") (pinfunction "P_47") (pintype "passive"))
    )
    (net (code "67") (name "RS485-4-B") (class "Default")
      (node (ref "U1") (pin "7") (pinfunction "B_7") (pintype "bidirectional"))
      (node (ref "X1") (pin "49") (pinfunction "P_49") (pintype "passive"))
    )
    (net (code "68") (name "RS485-4-Y") (class "Default")
      (node (ref "U1") (pin "5") (pinfunction "Y_5") (pintype "bidirectional"))
      (node (ref "X1") (pin "45") (pinfunction "P_45") (pintype "passive"))
    )
    (net (code "69") (name "RS485-4-Z") (class "Default")
      (node (ref "U1") (pin "6") (pinfunction "Z_6") (pintype "bidirectional"))
      (node (ref "X1") (pin "43") (pinfunction "P_43") (pintype "passive"))
    )
    (net (code "70") (name "RTD-HORN") (class "Default")
      (node (ref "R16") (pin "2") (pinfunction "2_2") (pintype "passive"))
    )
    (net (code "71") (name "RXD1") (class "Default")
      (node (ref "JP3") (pin "2") (pinfunction "2_2") (pintype "passive"))
      (node (ref "RX1") (pin "C") (pinfunction "C_C") (pintype "passive"))
      (node (ref "U3") (pin "2") (pinfunction "RO_2") (pintype "bidirectional"))
    )
    (net (code "72") (name "RXD2") (class "Default")
      (node (ref "JP4") (pin "2") (pinfunction "2_2") (pintype "passive"))
      (node (ref "RX3") (pin "C") (pinfunction "C_C") (pintype "passive"))
      (node (ref "U4") (pin "2") (pinfunction "RO_2") (pintype "bidirectional"))
    )
    (net (code "73") (name "RXD3") (class "Default")
      (node (ref "JP2") (pin "2") (pinfunction "2_2") (pintype "passive"))
      (node (ref "RX2") (pin "C") (pinfunction "C_C") (pintype "passive"))
      (node (ref "U2") (pin "2") (pinfunction "RO_2") (pintype "bidirectional"))
    )
    (net (code "74") (name "RXD4") (class "Default")
      (node (ref "JP1") (pin "2") (pinfunction "2_2") (pintype "passive"))
      (node (ref "RX4") (pin "C") (pinfunction "C_C") (pintype "passive"))
      (node (ref "U1") (pin "2") (pinfunction "RO_2") (pintype "bidirectional"))
    )
    (net (code "75") (name "SS") (class "Default")
      (node (ref "R7") (pin "1") (pinfunction "1_1") (pintype "passive"))
    )
    (net (code "76") (name "TXD1") (class "Default")
      (node (ref "JP3") (pin "1") (pinfunction "1_1") (pintype "passive"))
      (node (ref "TX1") (pin "C") (pinfunction "C_C") (pintype "passive"))
      (node (ref "U3") (pin "3") (pinfunction "DI_3") (pintype "bidirectional"))
    )
    (net (code "77") (name "TXD2") (class "Default")
      (node (ref "JP4") (pin "1") (pinfunction "1_1") (pintype "passive"))
      (node (ref "TX3") (pin "C") (pinfunction "C_C") (pintype "passive"))
      (node (ref "U4") (pin "3") (pinfunction "DI_3") (pintype "bidirectional"))
    )
    (net (code "78") (name "TXD3") (class "Default")
      (node (ref "JP2") (pin "1") (pinfunction "1_1") (pintype "passive"))
      (node (ref "TX2") (pin "C") (pinfunction "C_C") (pintype "passive"))
      (node (ref "U2") (pin "3") (pinfunction "DI_3") (pintype "bidirectional"))
    )
    (net (code "79") (name "TXD4") (class "Default")
      (node (ref "JP1") (pin "1") (pinfunction "1_1") (pintype "passive"))
      (node (ref "TX4") (pin "C") (pinfunction "C_C") (pintype "passive"))
      (node (ref "U1") (pin "3") (pinfunction "DI_3") (pintype "bidirectional"))
    )
    (net (code "80") (name "U1RX") (class "Default")
      (node (ref "U6") (pin "57") (pinfunction "PB14_57") (pintype "bidirectional"))
    )
    (net (code "81") (name "U1TX") (class "Default")
      (node (ref "U6") (pin "58") (pinfunction "PB15_58") (pintype "bidirectional"))
    )
    (net (code "82") (name "U3RX") (class "Default")
      (node (ref "U6") (pin "46") (pinfunction "PB09_46") (pintype "bidirectional"))
    )
    (net (code "83") (name "U3TX") (class "Default")
      (node (ref "U6") (pin "47") (pinfunction "PB10_47") (pintype "bidirectional"))
    )
    (net (code "84") (name "VBUSD") (class "Default")
      (node (ref "JP17") (pin "1") (pinfunction "1_1") (pintype "passive"))
      (node (ref "R14") (pin "1") (pinfunction "1_1") (pintype "passive"))
      (node (ref "R15") (pin "2") (pinfunction "2_2") (pintype "passive"))
    )
    (net (code "85") (name "VUSB") (class "Default")
      (node (ref "CN2") (pin "VBUS") (pinfunction "VBUS_VBUS") (pintype "power_in"))
      (node (ref "JP18") (pin "1") (pinfunction "1_1") (pintype "passive"))
      (node (ref "R14") (pin "2") (pinfunction "2_2") (pintype "passive"))
    )
    (net (code "86") (name "unconnected-(CN1-PadID)") (class "Default")
      (node (ref "CN1") (pin "ID") (pinfunction "ID_ID") (pintype "bidirectional"))
    )
    (net (code "87") (name "unconnected-(CN2-PadID)") (class "Default")
      (node (ref "CN2") (pin "ID") (pinfunction "ID_ID") (pintype "bidirectional"))
    )
    (net (code "88") (name "unconnected-(JP13-1-PadDTR)") (class "Default")
      (node (ref "JP13") (pin "DTR") (pinfunction "1_DTR") (pintype "passive"))
    )
    (net (code "89") (name "unconnected-(JP13-2-PadRXI)") (class "Default")
      (node (ref "JP13") (pin "RXI") (pinfunction "2_RXI") (pintype "passive"))
    )
    (net (code "90") (name "unconnected-(JP13-3-PadTXO)") (class "Default")
      (node (ref "JP13") (pin "TXO") (pinfunction "3_TXO") (pintype "passive"))
    )
    (net (code "91") (name "unconnected-(JP13-4-PadVCC)") (class "Default")
      (node (ref "JP13") (pin "VCC") (pinfunction "4_VCC") (pintype "passive"))
    )
    (net (code "92") (name "unconnected-(JP13-5-PadCTS)") (class "Default")
      (node (ref "JP13") (pin "CTS") (pinfunction "5_CTS") (pintype "passive"))
    )
    (net (code "93") (name "unconnected-(U5-CTS-Pad11)") (class "Default")
      (node (ref "U5") (pin "11") (pinfunction "CTS_11") (pintype "bidirectional"))
    )
    (net (code "94") (name "unconnected-(U5-DTR-Pad2)") (class "Default")
      (node (ref "U5") (pin "2") (pinfunction "DTR_2") (pintype "bidirectional"))
    )
    (net (code "95") (name "unconnected-(U5-RTS-Pad3)") (class "Default")
      (node (ref "U5") (pin "3") (pinfunction "RTS_3") (pintype "bidirectional"))
    )
    (net (code "96") (name "unconnected-(U6-PA04-Pad15)") (class "Default")
      (node (ref "U6") (pin "15") (pinfunction "PA04_15") (pintype "bidirectional"))
    )
    (net (code "97") (name "unconnected-(U6-PA05-Pad16)") (class "Default")
      (node (ref "U6") (pin "16") (pinfunction "PA05_16") (pintype "bidirectional"))
    )
    (net (code "98") (name "unconnected-(U6-PA06-Pad21)") (class "Default")
      (node (ref "U6") (pin "21") (pinfunction "PA06_21") (pintype "bidirectional"))
    )
    (net (code "99") (name "unconnected-(U6-PA07-Pad22)") (class "Default")
      (node (ref "U6") (pin "22") (pinfunction "PA07_22") (pintype "bidirectional"))
    )
    (net (code "100") (name "unconnected-(U6-PA08-Pad26)") (class "Default")
      (node (ref "U6") (pin "26") (pinfunction "PA08_26") (pintype "bidirectional"))
    )
    (net (code "101") (name "unconnected-(U6-PA09-Pad29)") (class "Default")
      (node (ref "U6") (pin "29") (pinfunction "PA09_29") (pintype "bidirectional"))
    )
    (net (code "102") (name "unconnected-(U6-PA10-Pad30)") (class "Default")
      (node (ref "U6") (pin "30") (pinfunction "PA10_30") (pintype "bidirectional"))
    )
    (net (code "103") (name "unconnected-(U6-PA11-Pad31)") (class "Default")
      (node (ref "U6") (pin "31") (pinfunction "PA11_31") (pintype "bidirectional"))
    )
    (net (code "104") (name "unconnected-(U6-PA12-Pad32)") (class "Default")
      (node (ref "U6") (pin "32") (pinfunction "PA12_32") (pintype "bidirectional"))
    )
    (net (code "105") (name "unconnected-(U6-PA13-Pad40)") (class "Default")
      (node (ref "U6") (pin "40") (pinfunction "PA13_40") (pintype "bidirectional"))
    )
    (net (code "106") (name "unconnected-(U6-PA14-Pad41)") (class "Default")
      (node (ref "U6") (pin "41") (pinfunction "PA14_41") (pintype "bidirectional"))
    )
    (net (code "107") (name "unconnected-(U6-PA15-Pad42)") (class "Default")
      (node (ref "U6") (pin "42") (pinfunction "PA15_42") (pintype "bidirectional"))
    )
    (net (code "108") (name "unconnected-(U6-PA16-Pad43)") (class "Default")
      (node (ref "U6") (pin "43") (pinfunction "PA16_43") (pintype "bidirectional"))
    )
    (net (code "109") (name "unconnected-(U6-PA17-Pad44)") (class "Default")
      (node (ref "U6") (pin "44") (pinfunction "PA17_44") (pintype "bidirectional"))
    )
    (net (code "110") (name "unconnected-(U6-PA18-Pad49)") (class "Default")
      (node (ref "U6") (pin "49") (pinfunction "PA18_49") (pintype "bidirectional"))
    )
    (net (code "111") (name "unconnected-(U6-PA19-Pad50)") (class "Default")
      (node (ref "U6") (pin "50") (pinfunction "PA19_50") (pintype "bidirectional"))
    )
    (net (code "112") (name "unconnected-(U6-PA20-Pad51)") (class "Default")
      (node (ref "U6") (pin "51") (pinfunction "PA20_51") (pintype "bidirectional"))
    )
    (net (code "113") (name "unconnected-(U6-PA27-Pad33)") (class "Default")
      (node (ref "U6") (pin "33") (pinfunction "PA27_33") (pintype "bidirectional"))
    )
    (net (code "114") (name "unconnected-(U6-PA28-Pad34)") (class "Default")
      (node (ref "U6") (pin "34") (pinfunction "PA28_34") (pintype "bidirectional"))
    )
    (net (code "115") (name "unconnected-(U6-PA29-Pad35)") (class "Default")
      (node (ref "U6") (pin "35") (pinfunction "PA29_35") (pintype "bidirectional"))
    )
    (net (code "116") (name "unconnected-(U6-PA30-Pad38)") (class "Default")
      (node (ref "U6") (pin "38") (pinfunction "PA30_38") (pintype "bidirectional"))
    )
    (net (code "117") (name "unconnected-(U6-PA31-Pad39)") (class "Default")
      (node (ref "U6") (pin "39") (pinfunction "PA31_39") (pintype "bidirectional"))
    )
    (net (code "118") (name "unconnected-(U6-PB00-Pad11)") (class "Default")
      (node (ref "U6") (pin "11") (pinfunction "PB00_11") (pintype "bidirectional"))
    )
    (net (code "119") (name "unconnected-(U6-PB01-Pad12)") (class "Default")
      (node (ref "U6") (pin "12") (pinfunction "PB01_12") (pintype "bidirectional"))
    )
    (net (code "120") (name "unconnected-(U6-PB02-Pad13)") (class "Default")
      (node (ref "U6") (pin "13") (pinfunction "PB02_13") (pintype "bidirectional"))
    )
    (net (code "121") (name "unconnected-(U6-PB03-Pad14)") (class "Default")
      (node (ref "U6") (pin "14") (pinfunction "PB03_14") (pintype "bidirectional"))
    )
    (net (code "122") (name "unconnected-(U6-PB04-Pad19)") (class "Default")
      (node (ref "U6") (pin "19") (pinfunction "PB04_19") (pintype "bidirectional"))
    )
    (net (code "123") (name "unconnected-(U6-PB05-Pad20)") (class "Default")
      (node (ref "U6") (pin "20") (pinfunction "PB05_20") (pintype "bidirectional"))
    )
    (net (code "124") (name "unconnected-(U6-PB06-Pad27)") (class "Default")
      (node (ref "U6") (pin "27") (pinfunction "PB06_27") (pintype "bidirectional"))
    )
    (net (code "125") (name "unconnected-(U6-PB07-Pad28)") (class "Default")
      (node (ref "U6") (pin "28") (pinfunction "PB07_28") (pintype "bidirectional"))
    )
    (net (code "126") (name "unconnected-(U6-PB08-Pad45)") (class "Default")
      (node (ref "U6") (pin "45") (pinfunction "PB08_45") (pintype "bidirectional"))
    )
    (net (code "127") (name "unconnected-(U6-PB11-Pad48)") (class "Default")
      (node (ref "U6") (pin "48") (pinfunction "PB11_48") (pintype "bidirectional"))
    )
    (net (code "128") (name "unconnected-(U6-PB12-Pad53)") (class "Default")
      (node (ref "U6") (pin "53") (pinfunction "PB12_53") (pintype "bidirectional"))
    )
    (net (code "129") (name "unconnected-(U6-PB13-Pad54)") (class "Default")
      (node (ref "U6") (pin "54") (pinfunction "PB13_54") (pintype "bidirectional"))
    )
    (net (code "130") (name "unconnected-(U6-TCK-Pad9)") (class "Default")
      (node (ref "U6") (pin "9") (pinfunction "TCK_9") (pintype "bidirectional"))
    )
    (net (code "131") (name "unconnected-(U14-GND-Pad4)") (class "Default")
      (node (ref "U14") (pin "4") (pinfunction "GND_4") (pintype "bidirectional"))
    )
    (net (code "132") (name "unconnected-(X1AI-P-Pad18)") (class "Default")
      (node (ref "X1") (pin "18") (pinfunction "P_18") (pintype "passive"))
    )
    (net (code "133") (name "unconnected-(X1AL-P-Pad20)") (class "Default")
      (node (ref "X1") (pin "20") (pinfunction "P_20") (pintype "passive"))
    )
    (net (code "134") (name "unconnected-(X1AN-P-Pad22)") (class "Default")
      (node (ref "X1") (pin "22") (pinfunction "P_22") (pintype "passive"))
    )
    (net (code "135") (name "unconnected-(X1AP-P-Pad24)") (class "Default")
      (node (ref "X1") (pin "24") (pinfunction "P_24") (pintype "passive"))
    )
    (net (code "136") (name "unconnected-(X1AR-P-Pad26)") (class "Default")
      (node (ref "X1") (pin "26") (pinfunction "P_26") (pintype "passive"))
    )
    (net (code "137") (name "unconnected-(X1AT-P-Pad28)") (class "Default")
      (node (ref "X1") (pin "28") (pinfunction "P_28") (pintype "passive"))
    )
    (net (code "138") (name "unconnected-(X1AW-P-Pad30)") (class "Default")
      (node (ref "X1") (pin "30") (pinfunction "P_30") (pintype "passive"))
    )
    (net (code "139") (name "unconnected-(X1AY-P-Pad32)") (class "Default")
      (node (ref "X1") (pin "32") (pinfunction "P_32") (pintype "passive"))
    )
    (net (code "140") (name "unconnected-(X1BA-P-Pad34)") (class "Default")
      (node (ref "X1") (pin "34") (pinfunction "P_34") (pintype "passive"))
    )
    (net (code "141") (name "unconnected-(X1BC-P-Pad36)") (class "Default")
      (node (ref "X1") (pin "36") (pinfunction "P_36") (pintype "passive"))
    )
    (net (code "142") (name "unconnected-(X1BE-P-Pad38)") (class "Default")
      (node (ref "X1") (pin "38") (pinfunction "P_38") (pintype "passive"))
    )
    (net (code "143") (name "unconnected-(X1BH-P-Pad40)") (class "Default")
      (node (ref "X1") (pin "40") (pinfunction "P_40") (pintype "passive"))
    )
    (net (code "144") (name "unconnected-(X1BI-P-Pad41)") (class "Default")
      (node (ref "X1") (pin "41") (pinfunction "P_41") (pintype "passive"))
    )
    (net (code "145") (name "unconnected-(X1BJ-P-Pad42)") (class "Default")
      (node (ref "X1") (pin "42") (pinfunction "P_42") (pintype "passive"))
    )
    (net (code "146") (name "unconnected-(X1BL-P-Pad44)") (class "Default")
      (node (ref "X1") (pin "44") (pinfunction "P_44") (pintype "passive"))
    )
    (net (code "147") (name "unconnected-(X1BN-P-Pad46)") (class "Default")
      (node (ref "X1") (pin "46") (pinfunction "P_46") (pintype "passive"))
    )
    (net (code "148") (name "unconnected-(X1BP-P-Pad48)") (class "Default")
      (node (ref "X1") (pin "48") (pinfunction "P_48") (pintype "passive"))
    )
    (net (code "149") (name "unconnected-(X1BS-P-Pad50)") (class "Default")
      (node (ref "X1") (pin "50") (pinfunction "P_50") (pintype "passive"))
    )
    (net (code "150") (name "unconnected-(X1BT-P-Pad51)") (class "Default")
      (node (ref "X1") (pin "51") (pinfunction "P_51") (pintype "passive"))
    )
    (net (code "151") (name "unconnected-(X1BU-P-Pad52)") (class "Default")
      (node (ref "X1") (pin "52") (pinfunction "P_52") (pintype "passive"))
    )
    (net (code "152") (name "unconnected-(X1BV-P-Pad53)") (class "Default")
      (node (ref "X1") (pin "53") (pinfunction "P_53") (pintype "passive"))
    )
    (net (code "153") (name "unconnected-(X1BW-P-Pad54)") (class "Default")
      (node (ref "X1") (pin "54") (pinfunction "P_54") (pintype "passive"))
    )
    (net (code "154") (name "unconnected-(X1BX-P-Pad55)") (class "Default")
      (node (ref "X1") (pin "55") (pinfunction "P_55") (pintype "passive"))
    )
    (net (code "155") (name "unconnected-(X1BY-P-Pad56)") (class "Default")
      (node (ref "X1") (pin "56") (pinfunction "P_56") (pintype "passive"))
    )
    (net (code "156") (name "unconnected-(X1BZ-P-Pad57)") (class "Default")
      (node (ref "X1") (pin "57") (pinfunction "P_57") (pintype "passive"))
    )
    (net (code "157") (name "unconnected-(X1C-P-Pad100)") (class "Default")
      (node (ref "X1") (pin "100") (pinfunction "P_100") (pintype "passive"))
    )
    (net (code "158") (name "unconnected-(X1CA-P-Pad58)") (class "Default")
      (node (ref "X1") (pin "58") (pinfunction "P_58") (pintype "passive"))
    )
    (net (code "159") (name "unconnected-(X1CB-P-Pad59)") (class "Default")
      (node (ref "X1") (pin "59") (pinfunction "P_59") (pintype "passive"))
    )
    (net (code "160") (name "unconnected-(X1CD-P-Pad60)") (class "Default")
      (node (ref "X1") (pin "60") (pinfunction "P_60") (pintype "passive"))
    )
    (net (code "161") (name "unconnected-(X1CE-P-Pad61)") (class "Default")
      (node (ref "X1") (pin "61") (pinfunction "P_61") (pintype "passive"))
    )
    (net (code "162") (name "unconnected-(X1CF-P-Pad62)") (class "Default")
      (node (ref "X1") (pin "62") (pinfunction "P_62") (pintype "passive"))
    )
    (net (code "163") (name "unconnected-(X1CG-P-Pad63)") (class "Default")
      (node (ref "X1") (pin "63") (pinfunction "P_63") (pintype "passive"))
    )
    (net (code "164") (name "unconnected-(X1CH-P-Pad64)") (class "Default")
      (node (ref "X1") (pin "64") (pinfunction "P_64") (pintype "passive"))
    )
    (net (code "165") (name "unconnected-(X1CI-P-Pad65)") (class "Default")
      (node (ref "X1") (pin "65") (pinfunction "P_65") (pintype "passive"))
    )
    (net (code "166") (name "unconnected-(X1CJ-P-Pad66)") (class "Default")
      (node (ref "X1") (pin "66") (pinfunction "P_66") (pintype "passive"))
    )
    (net (code "167") (name "unconnected-(X1CK-P-Pad67)") (class "Default")
      (node (ref "X1") (pin "67") (pinfunction "P_67") (pintype "passive"))
    )
    (net (code "168") (name "unconnected-(X1CL-P-Pad68)") (class "Default")
      (node (ref "X1") (pin "68") (pinfunction "P_68") (pintype "passive"))
    )
    (net (code "169") (name "unconnected-(X1CM-P-Pad69)") (class "Default")
      (node (ref "X1") (pin "69") (pinfunction "P_69") (pintype "passive"))
    )
    (net (code "170") (name "unconnected-(X1CO-P-Pad70)") (class "Default")
      (node (ref "X1") (pin "70") (pinfunction "P_70") (pintype "passive"))
    )
    (net (code "171") (name "unconnected-(X1CP-P-Pad71)") (class "Default")
      (node (ref "X1") (pin "71") (pinfunction "P_71") (pintype "passive"))
    )
    (net (code "172") (name "unconnected-(X1CQ-P-Pad72)") (class "Default")
      (node (ref "X1") (pin "72") (pinfunction "P_72") (pintype "passive"))
    )
    (net (code "173") (name "unconnected-(X1CR-P-Pad73)") (class "Default")
      (node (ref "X1") (pin "73") (pinfunction "P_73") (pintype "passive"))
    )
    (net (code "174") (name "unconnected-(X1CS-P-Pad74)") (class "Default")
      (node (ref "X1") (pin "74") (pinfunction "P_74") (pintype "passive"))
    )
    (net (code "175") (name "unconnected-(X1CT-P-Pad75)") (class "Default")
      (node (ref "X1") (pin "75") (pinfunction "P_75") (pintype "passive"))
    )
    (net (code "176") (name "unconnected-(X1CU-P-Pad76)") (class "Default")
      (node (ref "X1") (pin "76") (pinfunction "P_76") (pintype "passive"))
    )
    (net (code "177") (name "unconnected-(X1CV-P-Pad77)") (class "Default")
      (node (ref "X1") (pin "77") (pinfunction "P_77") (pintype "passive"))
    )
    (net (code "178") (name "unconnected-(X1CW-P-Pad78)") (class "Default")
      (node (ref "X1") (pin "78") (pinfunction "P_78") (pintype "passive"))
    )
    (net (code "179") (name "unconnected-(X1CX-P-Pad79)") (class "Default")
      (node (ref "X1") (pin "79") (pinfunction "P_79") (pintype "passive"))
    )
    (net (code "180") (name "unconnected-(X1CZ-P-Pad80)") (class "Default")
      (node (ref "X1") (pin "80") (pinfunction "P_80") (pintype "passive"))
    )
    (net (code "181") (name "unconnected-(X1D-P-Pad101)") (class "Default")
      (node (ref "X1") (pin "101") (pinfunction "P_101") (pintype "passive"))
    )
    (net (code "182") (name "unconnected-(X1DA-P-Pad81)") (class "Default")
      (node (ref "X1") (pin "81") (pinfunction "P_81") (pintype "passive"))
    )
    (net (code "183") (name "unconnected-(X1DB-P-Pad82)") (class "Default")
      (node (ref "X1") (pin "82") (pinfunction "P_82") (pintype "passive"))
    )
    (net (code "184") (name "unconnected-(X1DC-P-Pad83)") (class "Default")
      (node (ref "X1") (pin "83") (pinfunction "P_83") (pintype "passive"))
    )
    (net (code "185") (name "unconnected-(X1DD-P-Pad84)") (class "Default")
      (node (ref "X1") (pin "84") (pinfunction "P_84") (pintype "passive"))
    )
    (net (code "186") (name "unconnected-(X1DE-P-Pad85)") (class "Default")
      (node (ref "X1") (pin "85") (pinfunction "P_85") (pintype "passive"))
    )
    (net (code "187") (name "unconnected-(X1DF-P-Pad86)") (class "Default")
      (node (ref "X1") (pin "86") (pinfunction "P_86") (pintype "passive"))
    )
    (net (code "188") (name "unconnected-(X1DG-P-Pad87)") (class "Default")
      (node (ref "X1") (pin "87") (pinfunction "P_87") (pintype "passive"))
    )
    (net (code "189") (name "unconnected-(X1DH-P-Pad88)") (class "Default")
      (node (ref "X1") (pin "88") (pinfunction "P_88") (pintype "passive"))
    )
    (net (code "190") (name "unconnected-(X1DI-P-Pad89)") (class "Default")
      (node (ref "X1") (pin "89") (pinfunction "P_89") (pintype "passive"))
    )
    (net (code "191") (name "unconnected-(X1DK-P-Pad90)") (class "Default")
      (node (ref "X1") (pin "90") (pinfunction "P_90") (pintype "passive"))
    )
    (net (code "192") (name "unconnected-(X1DL-P-Pad91)") (class "Default")
      (node (ref "X1") (pin "91") (pinfunction "P_91") (pintype "passive"))
    )
    (net (code "193") (name "unconnected-(X1DM-P-Pad92)") (class "Default")
      (node (ref "X1") (pin "92") (pinfunction "P_92") (pintype "passive"))
    )
    (net (code "194") (name "unconnected-(X1DN-P-Pad93)") (class "Default")
      (node (ref "X1") (pin "93") (pinfunction "P_93") (pintype "passive"))
    )
    (net (code "195") (name "unconnected-(X1DO-P-Pad94)") (class "Default")
      (node (ref "X1") (pin "94") (pinfunction "P_94") (pintype "passive"))
    )
    (net (code "196") (name "unconnected-(X1DP-P-Pad95)") (class "Default")
      (node (ref "X1") (pin "95") (pinfunction "P_95") (pintype "passive"))
    )
    (net (code "197") (name "unconnected-(X1DQ-P-Pad96)") (class "Default")
      (node (ref "X1") (pin "96") (pinfunction "P_96") (pintype "passive"))
    )
    (net (code "198") (name "unconnected-(X1DR-P-Pad97)") (class "Default")
      (node (ref "X1") (pin "97") (pinfunction "P_97") (pintype "passive"))
    )
    (net (code "199") (name "unconnected-(X1DS-P-Pad98)") (class "Default")
      (node (ref "X1") (pin "98") (pinfunction "P_98") (pintype "passive"))
    )
    (net (code "200") (name "unconnected-(X1DT-P-Pad99)") (class "Default")
      (node (ref "X1") (pin "99") (pinfunction "P_99") (pintype "passive"))
    )
    (net (code "201") (name "unconnected-(X1E-P-Pad102)") (class "Default")
      (node (ref "X1") (pin "102") (pinfunction "P_102") (pintype "passive"))
    )
    (net (code "202") (name "unconnected-(X1F-P-Pad103)") (class "Default")
      (node (ref "X1") (pin "103") (pinfunction "P_103") (pintype "passive"))
    )
    (net (code "203") (name "unconnected-(X1G-P-Pad104)") (class "Default")
      (node (ref "X1") (pin "104") (pinfunction "P_104") (pintype "passive"))
    )
    (net (code "204") (name "unconnected-(X1H-P-Pad105)") (class "Default")
      (node (ref "X1") (pin "105") (pinfunction "P_105") (pintype "passive"))
    )
    (net (code "205") (name "unconnected-(X1I-P-Pad106)") (class "Default")
      (node (ref "X1") (pin "106") (pinfunction "P_106") (pintype "passive"))
    )
    (net (code "206") (name "unconnected-(X1J-P-Pad107)") (class "Default")
      (node (ref "X1") (pin "107") (pinfunction "P_107") (pintype "passive"))
    )
    (net (code "207") (name "unconnected-(X1K-P-Pad108)") (class "Default")
      (node (ref "X1") (pin "108") (pinfunction "P_108") (pintype "passive"))
    )
    (net (code "208") (name "unconnected-(X1L-P-Pad109)") (class "Default")
      (node (ref "X1") (pin "109") (pinfunction "P_109") (pintype "passive"))
    )
    (net (code "209") (name "unconnected-(X1N-P-Pad110)") (class "Default")
      (node (ref "X1") (pin "110") (pinfunction "P_110") (pintype "passive"))
    )
    (net (code "210") (name "unconnected-(X1O-P-Pad111)") (class "Default")
      (node (ref "X1") (pin "111") (pinfunction "P_111") (pintype "passive"))
    )
    (net (code "211") (name "unconnected-(X1P-P-Pad112)") (class "Default")
      (node (ref "X1") (pin "112") (pinfunction "P_112") (pintype "passive"))
    )
    (net (code "212") (name "unconnected-(X1Q-P-Pad113)") (class "Default")
      (node (ref "X1") (pin "113") (pinfunction "P_113") (pintype "passive"))
    )
    (net (code "213") (name "unconnected-(X1R-P-Pad114)") (class "Default")
      (node (ref "X1") (pin "114") (pinfunction "P_114") (pintype "passive"))
    )
    (net (code "214") (name "unconnected-(X1S-P-Pad115)") (class "Default")
      (node (ref "X1") (pin "115") (pinfunction "P_115") (pintype "passive"))
    )
    (net (code "215") (name "unconnected-(X1T-P-Pad116)") (class "Default")
      (node (ref "X1") (pin "116") (pinfunction "P_116") (pintype "passive"))
    )
  )
)
